# 02_MCU_IO.net
KiCad netlist of a schematic drawn in Altium Designer
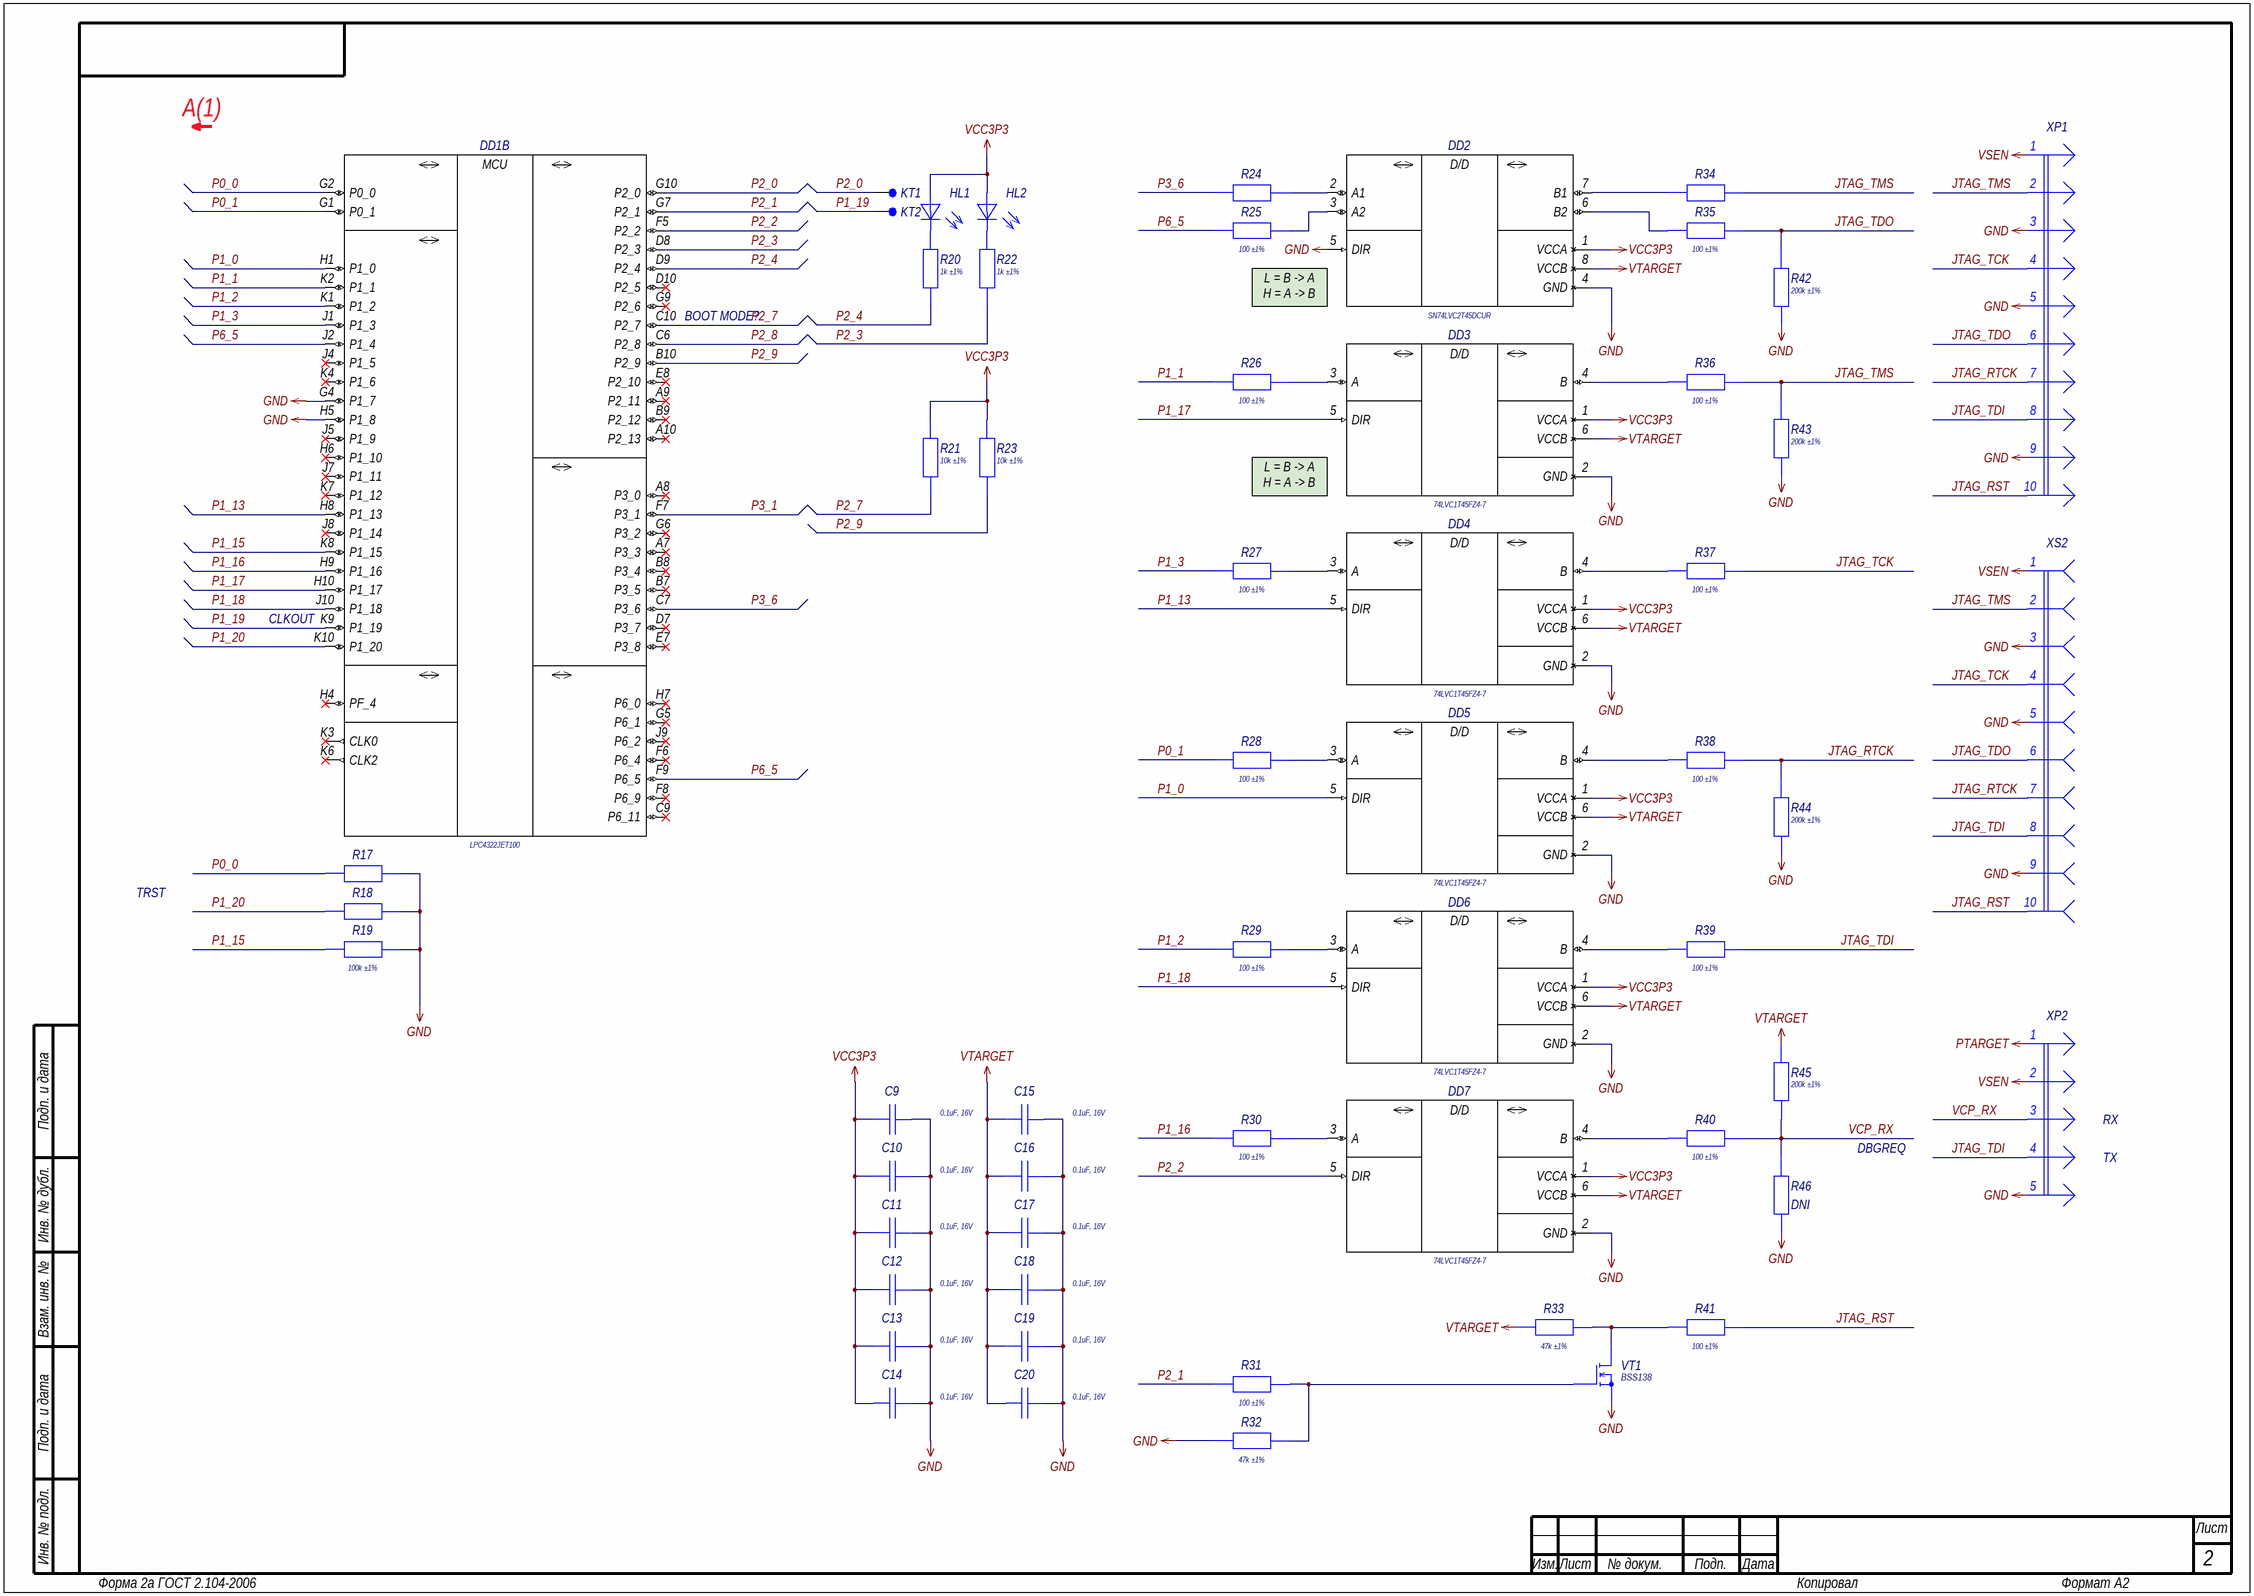
[diagram p0: 02_MCU_IO.SchDoc]

(export (version "E")
  (design (tool "Eeschema 10.0.6"))
  (components
    (comp (ref "C9")
      (value "Capacitor")
      (footprint "C0402_100X050H050_H")
      (fields
        (field (name "PART NUMBER") "GCM155R71C104KA55D")
        (field (name "VOLTAGE") "16V")
        (field (name "TOLERANCE") "±10%")
        (field (name "SCHEMATIC VALUE") "0.1uF, 16V")
      )
      (libsource (lib "ADLib") (part "Capacitor"))
    )
    (comp (ref "C10")
      (value "Capacitor")
      (footprint "C0402_100X050H050_H")
      (fields
        (field (name "PART NUMBER") "GCM155R71C104KA55D")
        (field (name "VOLTAGE") "16V")
        (field (name "TOLERANCE") "±10%")
        (field (name "SCHEMATIC VALUE") "0.1uF, 16V")
      )
      (libsource (lib "ADLib") (part "Capacitor"))
    )
    (comp (ref "C11")
      (value "Capacitor")
      (footprint "C0402_100X050H050_H")
      (fields
        (field (name "PART NUMBER") "GCM155R71C104KA55D")
        (field (name "VOLTAGE") "16V")
        (field (name "TOLERANCE") "±10%")
        (field (name "SCHEMATIC VALUE") "0.1uF, 16V")
      )
      (libsource (lib "ADLib") (part "Capacitor"))
    )
    (comp (ref "C12")
      (value "Capacitor")
      (footprint "C0402_100X050H050_H")
      (fields
        (field (name "PART NUMBER") "GCM155R71C104KA55D")
        (field (name "VOLTAGE") "16V")
        (field (name "TOLERANCE") "±10%")
        (field (name "SCHEMATIC VALUE") "0.1uF, 16V")
      )
      (libsource (lib "ADLib") (part "Capacitor"))
    )
    (comp (ref "C13")
      (value "Capacitor")
      (footprint "C0402_100X050H050_H")
      (fields
        (field (name "PART NUMBER") "GCM155R71C104KA55D")
        (field (name "VOLTAGE") "16V")
        (field (name "TOLERANCE") "±10%")
        (field (name "SCHEMATIC VALUE") "0.1uF, 16V")
      )
      (libsource (lib "ADLib") (part "Capacitor"))
    )
    (comp (ref "C14")
      (value "Capacitor")
      (footprint "C0402_100X050H050_H")
      (fields
        (field (name "PART NUMBER") "GCM155R71C104KA55D")
        (field (name "VOLTAGE") "16V")
        (field (name "TOLERANCE") "±10%")
        (field (name "SCHEMATIC VALUE") "0.1uF, 16V")
      )
      (libsource (lib "ADLib") (part "Capacitor"))
    )
    (comp (ref "C15")
      (value "Capacitor")
      (footprint "C0402_100X050H050_H")
      (fields
        (field (name "PART NUMBER") "GCM155R71C104KA55D")
        (field (name "VOLTAGE") "16V")
        (field (name "TOLERANCE") "±10%")
        (field (name "SCHEMATIC VALUE") "0.1uF, 16V")
      )
      (libsource (lib "ADLib") (part "Capacitor"))
    )
    (comp (ref "C16")
      (value "Capacitor")
      (footprint "C0402_100X050H050_H")
      (fields
        (field (name "PART NUMBER") "GCM155R71C104KA55D")
        (field (name "VOLTAGE") "16V")
        (field (name "TOLERANCE") "±10%")
        (field (name "SCHEMATIC VALUE") "0.1uF, 16V")
      )
      (libsource (lib "ADLib") (part "Capacitor"))
    )
    (comp (ref "C17")
      (value "Capacitor")
      (footprint "C0402_100X050H050_H")
      (fields
        (field (name "PART NUMBER") "GCM155R71C104KA55D")
        (field (name "VOLTAGE") "16V")
        (field (name "TOLERANCE") "±10%")
        (field (name "SCHEMATIC VALUE") "0.1uF, 16V")
      )
      (libsource (lib "ADLib") (part "Capacitor"))
    )
    (comp (ref "C18")
      (value "Capacitor")
      (footprint "C0402_100X050H050_H")
      (fields
        (field (name "PART NUMBER") "GCM155R71C104KA55D")
        (field (name "VOLTAGE") "16V")
        (field (name "TOLERANCE") "±10%")
        (field (name "SCHEMATIC VALUE") "0.1uF, 16V")
      )
      (libsource (lib "ADLib") (part "Capacitor"))
    )
    (comp (ref "C19")
      (value "Capacitor")
      (footprint "C0402_100X050H050_H")
      (fields
        (field (name "PART NUMBER") "GCM155R71C104KA55D")
        (field (name "VOLTAGE") "16V")
        (field (name "TOLERANCE") "±10%")
        (field (name "SCHEMATIC VALUE") "0.1uF, 16V")
      )
      (libsource (lib "ADLib") (part "Capacitor"))
    )
    (comp (ref "C20")
      (value "Capacitor")
      (footprint "C0402_100X050H050_H")
      (fields
        (field (name "PART NUMBER") "GCM155R71C104KA55D")
        (field (name "VOLTAGE") "16V")
        (field (name "TOLERANCE") "±10%")
        (field (name "SCHEMATIC VALUE") "0.1uF, 16V")
      )
      (libsource (lib "ADLib") (part "Capacitor"))
    )
    (comp (ref "DD1")
      (value "LPC43xxJET100-Series")
      (footprint "TFBGA-100_080P900X900X120_N")
      (fields
        (field (name "SCHEMATIC VALUE") "LPC4322JET100")
        (field (name "PART NUMBER") "LPC4322JET100")
        (field (name "MANUFACTURER") "NXP Semiconductors")
      )
      (libsource (lib "ADLib") (part "LPC43xxJET100-Series"))
    )
    (comp (ref "DD2")
      (value "SN74LVC2T45DCx-Series")
      (footprint "VSSOP-8_050P200X230X090_N")
      (fields
        (field (name "PART NUMBER") "SN74LVC2T45DCUR")
        (field (name "LCSC PART") "C15741")
        (field (name "MANUFACTURER") "Texas Instruments")
        (field (name "SCHEMATIC VALUE") "SN74LVC2T45DCUR")
      )
      (libsource (lib "ADLib") (part "SN74LVC2T45DCx-Series"))
    )
    (comp (ref "DD3")
      (value "74LVC1T45x-Series")
      (footprint "X2-DFN-6_050P140X100X040_N")
      (fields
        (field (name "PART NUMBER") "74LVC1T45FZ4-7")
        (field (name "LCSC PART") "C150482")
        (field (name "MANUFACTURER") "Diodes Incorporated")
        (field (name "SCHEMATIC VALUE") "74LVC1T45FZ4-7")
      )
      (libsource (lib "ADLib") (part "74LVC1T45x-Series"))
    )
    (comp (ref "DD4")
      (value "74LVC1T45x-Series")
      (footprint "X2-DFN-6_050P140X100X040_N")
      (fields
        (field (name "PART NUMBER") "74LVC1T45FZ4-7")
        (field (name "LCSC PART") "C150482")
        (field (name "MANUFACTURER") "Diodes Incorporated")
        (field (name "SCHEMATIC VALUE") "74LVC1T45FZ4-7")
      )
      (libsource (lib "ADLib") (part "74LVC1T45x-Series"))
    )
    (comp (ref "DD5")
      (value "74LVC1T45x-Series")
      (footprint "X2-DFN-6_050P140X100X040_N")
      (fields
        (field (name "PART NUMBER") "74LVC1T45FZ4-7")
        (field (name "LCSC PART") "C150482")
        (field (name "MANUFACTURER") "Diodes Incorporated")
        (field (name "SCHEMATIC VALUE") "74LVC1T45FZ4-7")
      )
      (libsource (lib "ADLib") (part "74LVC1T45x-Series"))
    )
    (comp (ref "DD6")
      (value "74LVC1T45x-Series")
      (footprint "X2-DFN-6_050P140X100X040_N")
      (fields
        (field (name "PART NUMBER") "74LVC1T45FZ4-7")
        (field (name "LCSC PART") "C150482")
        (field (name "MANUFACTURER") "Diodes Incorporated")
        (field (name "SCHEMATIC VALUE") "74LVC1T45FZ4-7")
      )
      (libsource (lib "ADLib") (part "74LVC1T45x-Series"))
    )
    (comp (ref "DD7")
      (value "74LVC1T45x-Series")
      (footprint "X2-DFN-6_050P140X100X040_N")
      (fields
        (field (name "PART NUMBER") "74LVC1T45FZ4-7")
        (field (name "LCSC PART") "C150482")
        (field (name "MANUFACTURER") "Diodes Incorporated")
        (field (name "SCHEMATIC VALUE") "74LVC1T45FZ4-7")
      )
      (libsource (lib "ADLib") (part "74LVC1T45x-Series"))
    )
    (comp (ref "HL1")
      (value "Text")
      (footprint "LD0603_L")
      (fields
        (field (name "PART NUMBER") "NCD0603R1")
        (field (name "LCSC PART") "C84263")
        (field (name "MANUFACTURER") "Foshan NationStar Optoelectronics")
        (field (name "PUBLISHER") "Andrew Danich")
      )
      (libsource (lib "ADLib") (part "Led-1"))
    )
    (comp (ref "HL2")
      (value "Text")
      (footprint "LD0603_L")
      (fields
        (field (name "PART NUMBER") "NCD0603G1")
        (field (name "LCSC PART") "C84267")
        (field (name "MANUFACTURER") "Foshan NationStar Optoelectronics")
        (field (name "PUBLISHER") "Andrew Danich")
      )
      (libsource (lib "ADLib") (part "Led-1"))
    )
    (comp (ref "KT1")
      (value "Text")
      (footprint "TP-SMT-C-0.5mm")
      (fields (field (name "PART NUMBER") "TestPoint-SMT") (field (name "PUBLISHER") "Andrew Danich"))
      (libsource (lib "ADLib") (part "TP-S-1"))
    )
    (comp (ref "KT2")
      (value "Text")
      (footprint "TP-SMT-C-0.5mm")
      (fields (field (name "PART NUMBER") "TestPoint-SMT") (field (name "PUBLISHER") "Andrew Danich"))
      (libsource (lib "ADLib") (part "TP-S-1"))
    )
    (comp (ref "R17")
      (value "Resistor")
      (footprint "R0402_100X050H035_H")
      (fields
        (field (name "PART NUMBER") "0402WGF1003TCE")
        (field (name "TOLERANCE") "±1%")
        (field (name "MANUFACTURER") "Uniroyal Elec")
      )
      (libsource (lib "ADLib") (part "Resistor"))
    )
    (comp (ref "R18")
      (value "Resistor")
      (footprint "R0402_100X050H035_H")
      (fields
        (field (name "PART NUMBER") "0402WGF1003TCE")
        (field (name "TOLERANCE") "±1%")
        (field (name "MANUFACTURER") "Uniroyal Elec")
      )
      (libsource (lib "ADLib") (part "Resistor"))
    )
    (comp (ref "R19")
      (value "Resistor")
      (footprint "R0402_100X050H035_H")
      (fields
        (field (name "PART NUMBER") "0402WGF1003TCE")
        (field (name "TOLERANCE") "±1%")
        (field (name "MANUFACTURER") "Uniroyal Elec")
        (field (name "SCHEMATIC VALUE") "100k ±1%")
      )
      (libsource (lib "ADLib") (part "Resistor"))
    )
    (comp (ref "R20")
      (value "Resistor")
      (footprint "R0402_100X050H035_H")
      (fields
        (field (name "PART NUMBER") "0402WGF1001TCE")
        (field (name "TOLERANCE") "±1%")
        (field (name "MANUFACTURER") "Uniroyal Elec")
        (field (name "SCHEMATIC VALUE") "1k ±1%")
      )
      (libsource (lib "ADLib") (part "Resistor"))
    )
    (comp (ref "R21")
      (value "Resistor")
      (footprint "R0402_100X050H035_H")
      (fields
        (field (name "PART NUMBER") "0402WGF1002TCE")
        (field (name "TOLERANCE") "±1%")
        (field (name "MANUFACTURER") "Uniroyal Elec")
        (field (name "SCHEMATIC VALUE") "10k ±1%")
      )
      (libsource (lib "ADLib") (part "Resistor"))
    )
    (comp (ref "R22")
      (value "Resistor")
      (footprint "R0402_100X050H035_H")
      (fields
        (field (name "PART NUMBER") "0402WGF1001TCE")
        (field (name "TOLERANCE") "±1%")
        (field (name "MANUFACTURER") "Uniroyal Elec")
        (field (name "SCHEMATIC VALUE") "1k ±1%")
      )
      (libsource (lib "ADLib") (part "Resistor"))
    )
    (comp (ref "R23")
      (value "Resistor")
      (footprint "R0402_100X050H035_H")
      (fields
        (field (name "PART NUMBER") "0402WGF1002TCE")
        (field (name "TOLERANCE") "±1%")
        (field (name "MANUFACTURER") "Uniroyal Elec")
        (field (name "SCHEMATIC VALUE") "10k ±1%")
      )
      (libsource (lib "ADLib") (part "Resistor"))
    )
    (comp (ref "R24")
      (value "Resistor")
      (footprint "R0402_100X050H035_H")
      (fields
        (field (name "PART NUMBER") "RC0402FR-07100RL")
        (field (name "TOLERANCE") "±1%")
        (field (name "MANUFACTURER") "Yageo")
      )
      (libsource (lib "ADLib") (part "Resistor"))
    )
    (comp (ref "R25")
      (value "Resistor")
      (footprint "R0402_100X050H035_H")
      (fields
        (field (name "PART NUMBER") "RC0402FR-07100RL")
        (field (name "TOLERANCE") "±1%")
        (field (name "MANUFACTURER") "Yageo")
        (field (name "SCHEMATIC VALUE") "100 ±1%")
      )
      (libsource (lib "ADLib") (part "Resistor"))
    )
    (comp (ref "R26")
      (value "Resistor")
      (footprint "R0402_100X050H035_H")
      (fields
        (field (name "PART NUMBER") "RC0402FR-07100RL")
        (field (name "TOLERANCE") "±1%")
        (field (name "MANUFACTURER") "Yageo")
        (field (name "SCHEMATIC VALUE") "100 ±1%")
      )
      (libsource (lib "ADLib") (part "Resistor"))
    )
    (comp (ref "R27")
      (value "Resistor")
      (footprint "R0402_100X050H035_H")
      (fields
        (field (name "PART NUMBER") "RC0402FR-07100RL")
        (field (name "TOLERANCE") "±1%")
        (field (name "MANUFACTURER") "Yageo")
        (field (name "SCHEMATIC VALUE") "100 ±1%")
      )
      (libsource (lib "ADLib") (part "Resistor"))
    )
    (comp (ref "R28")
      (value "Resistor")
      (footprint "R0402_100X050H035_H")
      (fields
        (field (name "PART NUMBER") "RC0402FR-07100RL")
        (field (name "TOLERANCE") "±1%")
        (field (name "MANUFACTURER") "Yageo")
        (field (name "SCHEMATIC VALUE") "100 ±1%")
      )
      (libsource (lib "ADLib") (part "Resistor"))
    )
    (comp (ref "R29")
      (value "Resistor")
      (footprint "R0402_100X050H035_H")
      (fields
        (field (name "PART NUMBER") "RC0402FR-07100RL")
        (field (name "TOLERANCE") "±1%")
        (field (name "MANUFACTURER") "Yageo")
        (field (name "SCHEMATIC VALUE") "100 ±1%")
      )
      (libsource (lib "ADLib") (part "Resistor"))
    )
    (comp (ref "R30")
      (value "Resistor")
      (footprint "R0402_100X050H035_H")
      (fields
        (field (name "PART NUMBER") "RC0402FR-07100RL")
        (field (name "TOLERANCE") "±1%")
        (field (name "MANUFACTURER") "Yageo")
        (field (name "SCHEMATIC VALUE") "100 ±1%")
      )
      (libsource (lib "ADLib") (part "Resistor"))
    )
    (comp (ref "R31")
      (value "Resistor")
      (footprint "R0402_100X050H035_H")
      (fields
        (field (name "PART NUMBER") "RC0402FR-07100RL")
        (field (name "TOLERANCE") "±1%")
        (field (name "MANUFACTURER") "Yageo")
        (field (name "SCHEMATIC VALUE") "100 ±1%")
      )
      (libsource (lib "ADLib") (part "Resistor"))
    )
    (comp (ref "R32")
      (value "Resistor")
      (footprint "R0402_100X050H035_H")
      (fields
        (field (name "PART NUMBER") "0402WGF4702TCE")
        (field (name "TOLERANCE") "±1%")
        (field (name "MANUFACTURER") "Uniroyal Elec")
        (field (name "SCHEMATIC VALUE") "47k ±1%")
      )
      (libsource (lib "ADLib") (part "Resistor"))
    )
    (comp (ref "R33")
      (value "Resistor")
      (footprint "R0402_100X050H035_H")
      (fields
        (field (name "PART NUMBER") "0402WGF4702TCE")
        (field (name "TOLERANCE") "±1%")
        (field (name "MANUFACTURER") "Uniroyal Elec")
        (field (name "SCHEMATIC VALUE") "47k ±1%")
      )
      (libsource (lib "ADLib") (part "Resistor"))
    )
    (comp (ref "R34")
      (value "Resistor")
      (footprint "R0402_100X050H035_H")
      (fields
        (field (name "PART NUMBER") "RC0402FR-07100RL")
        (field (name "TOLERANCE") "±1%")
        (field (name "MANUFACTURER") "Yageo")
      )
      (libsource (lib "ADLib") (part "Resistor"))
    )
    (comp (ref "R35")
      (value "Resistor")
      (footprint "R0402_100X050H035_H")
      (fields
        (field (name "PART NUMBER") "RC0402FR-07100RL")
        (field (name "TOLERANCE") "±1%")
        (field (name "MANUFACTURER") "Yageo")
        (field (name "SCHEMATIC VALUE") "100 ±1%")
      )
      (libsource (lib "ADLib") (part "Resistor"))
    )
    (comp (ref "R36")
      (value "Resistor")
      (footprint "R0402_100X050H035_H")
      (fields
        (field (name "PART NUMBER") "RC0402FR-07100RL")
        (field (name "TOLERANCE") "±1%")
        (field (name "MANUFACTURER") "Yageo")
        (field (name "SCHEMATIC VALUE") "100 ±1%")
      )
      (libsource (lib "ADLib") (part "Resistor"))
    )
    (comp (ref "R37")
      (value "Resistor")
      (footprint "R0402_100X050H035_H")
      (fields
        (field (name "PART NUMBER") "RC0402FR-07100RL")
        (field (name "TOLERANCE") "±1%")
        (field (name "MANUFACTURER") "Yageo")
        (field (name "SCHEMATIC VALUE") "100 ±1%")
      )
      (libsource (lib "ADLib") (part "Resistor"))
    )
    (comp (ref "R38")
      (value "Resistor")
      (footprint "R0402_100X050H035_H")
      (fields
        (field (name "PART NUMBER") "RC0402FR-07100RL")
        (field (name "TOLERANCE") "±1%")
        (field (name "MANUFACTURER") "Yageo")
        (field (name "SCHEMATIC VALUE") "100 ±1%")
      )
      (libsource (lib "ADLib") (part "Resistor"))
    )
    (comp (ref "R39")
      (value "Resistor")
      (footprint "R0402_100X050H035_H")
      (fields
        (field (name "PART NUMBER") "RC0402FR-07100RL")
        (field (name "TOLERANCE") "±1%")
        (field (name "MANUFACTURER") "Yageo")
        (field (name "SCHEMATIC VALUE") "100 ±1%")
      )
      (libsource (lib "ADLib") (part "Resistor"))
    )
    (comp (ref "R40")
      (value "Resistor")
      (footprint "R0402_100X050H035_H")
      (fields
        (field (name "PART NUMBER") "RC0402FR-07100RL")
        (field (name "TOLERANCE") "±1%")
        (field (name "MANUFACTURER") "Yageo")
        (field (name "SCHEMATIC VALUE") "100 ±1%")
      )
      (libsource (lib "ADLib") (part "Resistor"))
    )
    (comp (ref "R41")
      (value "Resistor")
      (footprint "R0402_100X050H035_H")
      (fields
        (field (name "PART NUMBER") "RC0402FR-07100RL")
        (field (name "TOLERANCE") "±1%")
        (field (name "MANUFACTURER") "Yageo")
        (field (name "SCHEMATIC VALUE") "100 ±1%")
      )
      (libsource (lib "ADLib") (part "Resistor"))
    )
    (comp (ref "R42")
      (value "Resistor")
      (footprint "R0402_100X050H035_H")
      (fields
        (field (name "PART NUMBER") "0402WGF2003TCE")
        (field (name "TOLERANCE") "±1%")
        (field (name "MANUFACTURER") "Uniroyal Elec")
        (field (name "SCHEMATIC VALUE") "200k ±1%")
      )
      (libsource (lib "ADLib") (part "Resistor"))
    )
    (comp (ref "R43")
      (value "Resistor")
      (footprint "R0402_100X050H035_H")
      (fields
        (field (name "PART NUMBER") "0402WGF2003TCE")
        (field (name "TOLERANCE") "±1%")
        (field (name "MANUFACTURER") "Uniroyal Elec")
        (field (name "SCHEMATIC VALUE") "200k ±1%")
      )
      (libsource (lib "ADLib") (part "Resistor"))
    )
    (comp (ref "R44")
      (value "Resistor")
      (footprint "R0402_100X050H035_H")
      (fields
        (field (name "PART NUMBER") "0402WGF2003TCE")
        (field (name "TOLERANCE") "±1%")
        (field (name "MANUFACTURER") "Uniroyal Elec")
        (field (name "SCHEMATIC VALUE") "200k ±1%")
      )
      (libsource (lib "ADLib") (part "Resistor"))
    )
    (comp (ref "R45")
      (value "Resistor")
      (footprint "R0402_100X050H035_H")
      (fields
        (field (name "PART NUMBER") "0402WGF2003TCE")
        (field (name "TOLERANCE") "±1%")
        (field (name "MANUFACTURER") "Uniroyal Elec")
        (field (name "SCHEMATIC VALUE") "200k ±1%")
      )
      (libsource (lib "ADLib") (part "Resistor"))
    )
    (comp (ref "R46")
      (value "Resistor")
      (footprint "R0402_100X050H035_H")
      (fields
        (field (name "PART NUMBER") "0402WGF2003TCE")
        (field (name "TOLERANCE") "±1%")
        (field (name "MANUFACTURER") "Uniroyal Elec")
      )
      (libsource (lib "ADLib") (part "Resistor"))
    )
    (comp (ref "VT1")
      (value "MOSFET-N_32")
      (footprint "SOT-23_190P290X160X145_N")
      (fields
        (field (name "SCHEMATIC VALUE") "BSS138")
        (field (name "PART NUMBER") "BSS138")
        (field (name "PUBLISHER") "Andrew Danich")
      )
      (libsource (lib "ADLib") (part "MOSFET-N_32"))
    )
    (comp (ref "XP1")
      (value "Text")
      (footprint "IDC-10MR")
      (fields (field (name "PART NUMBER") "IDC-10MR"))
      (libsource (lib "ADLib") (part "Con-10-M"))
    )
    (comp (ref "XP2")
      (value "Text")
      (footprint "PLS-5RR")
      (fields (field (name "PART NUMBER") "PLS-5R"))
      (libsource (lib "ADLib") (part "Con-5-M"))
    )
    (comp (ref "XS2")
      (value "Text")
      (footprint "XF2M-1015-1A")
      (fields (field (name "PART NUMBER") "XF2M-1015-1A") (field (name "MANUFACTURER") "Omron Electronics"))
      (libsource (lib "ADLib") (part "Con-10-F"))
    )
  )
  (nets
    (net (code "1") (name "/JTAG_RST") (class "Default")
      (node (ref "R41") (pin "2") (pinfunction "2_2") (pintype "passive"))
      (node (ref "XP1") (pin "10") (pintype "passive"))
      (node (ref "XS2") (pin "10") (pintype "passive"))
    )
    (net (code "2") (name "/JTAG_RTCK") (class "Default")
      (node (ref "R38") (pin "2") (pinfunction "2_2") (pintype "passive"))
      (node (ref "R44") (pin "2") (pinfunction "2_2") (pintype "passive"))
      (node (ref "XP1") (pin "7") (pintype "passive"))
      (node (ref "XS2") (pin "7") (pintype "passive"))
    )
    (net (code "3") (name "/JTAG_TCK") (class "Default")
      (node (ref "R37") (pin "2") (pinfunction "2_2") (pintype "passive"))
      (node (ref "XP1") (pin "4") (pintype "passive"))
      (node (ref "XS2") (pin "4") (pintype "passive"))
    )
    (net (code "4") (name "/JTAG_TDI") (class "Default")
      (node (ref "R39") (pin "2") (pinfunction "2_2") (pintype "passive"))
      (node (ref "XP1") (pin "8") (pintype "passive"))
      (node (ref "XP2") (pin "4") (pintype "passive"))
      (node (ref "XS2") (pin "8") (pintype "passive"))
    )
    (net (code "5") (name "/JTAG_TDO") (class "Default")
      (node (ref "R35") (pin "2") (pinfunction "2_2") (pintype "passive"))
      (node (ref "R42") (pin "2") (pinfunction "2_2") (pintype "passive"))
      (node (ref "XP1") (pin "6") (pintype "passive"))
      (node (ref "XS2") (pin "6") (pintype "passive"))
    )
    (net (code "6") (name "/JTAG_TMS") (class "Default")
      (node (ref "R34") (pin "2") (pinfunction "2_2") (pintype "passive"))
      (node (ref "R36") (pin "2") (pinfunction "2_2") (pintype "passive"))
      (node (ref "R43") (pin "2") (pinfunction "2_2") (pintype "passive"))
      (node (ref "XP1") (pin "2") (pintype "passive"))
      (node (ref "XS2") (pin "2") (pintype "passive"))
    )
    (net (code "7") (name "/P0_0") (class "Default")
      (node (ref "DD1") (pin "G2") (pinfunction "P0_0_G2") (pintype "bidirectional"))
      (node (ref "R17") (pin "1") (pinfunction "1_1") (pintype "passive"))
    )
    (net (code "8") (name "/P0_1") (class "Default")
      (node (ref "DD1") (pin "G1") (pinfunction "P0_1_G1") (pintype "bidirectional"))
      (node (ref "R28") (pin "1") (pinfunction "1_1") (pintype "passive"))
    )
    (net (code "9") (name "/P1_0") (class "Default")
      (node (ref "DD1") (pin "H1") (pinfunction "P1_0_H1") (pintype "bidirectional"))
      (node (ref "DD5") (pin "5") (pinfunction "DIR_5") (pintype "input"))
    )
    (net (code "10") (name "/P1_1") (class "Default")
      (node (ref "DD1") (pin "K2") (pinfunction "P1_1_K2") (pintype "bidirectional"))
      (node (ref "R26") (pin "1") (pinfunction "1_1") (pintype "passive"))
    )
    (net (code "11") (name "/P1_2") (class "Default")
      (node (ref "DD1") (pin "K1") (pinfunction "P1_2_K1") (pintype "bidirectional"))
      (node (ref "R29") (pin "1") (pinfunction "1_1") (pintype "passive"))
    )
    (net (code "12") (name "/P1_3") (class "Default")
      (node (ref "DD1") (pin "J1") (pinfunction "P1_3_J1") (pintype "bidirectional"))
      (node (ref "R27") (pin "1") (pinfunction "1_1") (pintype "passive"))
    )
    (net (code "13") (name "/P1_13") (class "Default")
      (node (ref "DD1") (pin "H8") (pinfunction "P1_13_H8") (pintype "bidirectional"))
      (node (ref "DD4") (pin "5") (pinfunction "DIR_5") (pintype "input"))
    )
    (net (code "14") (name "/P1_15") (class "Default")
      (node (ref "DD1") (pin "K8") (pinfunction "P1_15_K8") (pintype "bidirectional"))
      (node (ref "R19") (pin "1") (pinfunction "1_1") (pintype "passive"))
    )
    (net (code "15") (name "/P1_16") (class "Default")
      (node (ref "DD1") (pin "H9") (pinfunction "P1_16_H9") (pintype "bidirectional"))
      (node (ref "R30") (pin "1") (pinfunction "1_1") (pintype "passive"))
    )
    (net (code "16") (name "/P1_17") (class "Default")
      (node (ref "DD1") (pin "H10") (pinfunction "P1_17_H10") (pintype "bidirectional"))
      (node (ref "DD3") (pin "5") (pinfunction "DIR_5") (pintype "input"))
    )
    (net (code "17") (name "/P1_18") (class "Default")
      (node (ref "DD1") (pin "J10") (pinfunction "P1_18_J10") (pintype "bidirectional"))
      (node (ref "DD6") (pin "5") (pinfunction "DIR_5") (pintype "input"))
    )
    (net (code "18") (name "/P1_19") (class "Default")
      (node (ref "DD1") (pin "K9") (pinfunction "P1_19_K9") (pintype "bidirectional"))
      (node (ref "KT2") (pin "1") (pinfunction "1_1") (pintype "passive"))
    )
    (net (code "19") (name "/P1_20") (class "Default")
      (node (ref "DD1") (pin "K10") (pinfunction "P1_20_K10") (pintype "bidirectional"))
      (node (ref "R18") (pin "1") (pinfunction "1_1") (pintype "passive"))
    )
    (net (code "20") (name "/P2_0") (class "Default")
      (node (ref "DD1") (pin "G10") (pinfunction "P2_0_G10") (pintype "bidirectional"))
      (node (ref "KT1") (pin "1") (pinfunction "1_1") (pintype "passive"))
    )
    (net (code "21") (name "/P2_1") (class "Default")
      (node (ref "DD1") (pin "G7") (pinfunction "P2_1_G7") (pintype "bidirectional"))
      (node (ref "R31") (pin "1") (pinfunction "1_1") (pintype "passive"))
    )
    (net (code "22") (name "/P2_2") (class "Default")
      (node (ref "DD1") (pin "F5") (pinfunction "P2_2_F5") (pintype "bidirectional"))
      (node (ref "DD7") (pin "5") (pinfunction "DIR_5") (pintype "input"))
    )
    (net (code "23") (name "/P2_3") (class "Default")
      (node (ref "DD1") (pin "D8") (pinfunction "P2_3_D8") (pintype "bidirectional"))
      (node (ref "R22") (pin "1") (pinfunction "1_1") (pintype "passive"))
    )
    (net (code "24") (name "/P2_4") (class "Default")
      (node (ref "DD1") (pin "D9") (pinfunction "P2_4_D9") (pintype "bidirectional"))
      (node (ref "R20") (pin "1") (pinfunction "1_1") (pintype "passive"))
    )
    (net (code "25") (name "/P2_7") (class "Default")
      (node (ref "DD1") (pin "C10") (pinfunction "P2_7_C10") (pintype "bidirectional"))
      (node (ref "R21") (pin "2") (pinfunction "2_2") (pintype "passive"))
    )
    (net (code "26") (name "/P2_8") (class "Default")
      (node (ref "DD1") (pin "C6") (pinfunction "P2_8_C6") (pintype "bidirectional"))
    )
    (net (code "27") (name "/P2_9") (class "Default")
      (node (ref "DD1") (pin "B10") (pinfunction "P2_9_B10") (pintype "bidirectional"))
      (node (ref "R23") (pin "2") (pinfunction "2_2") (pintype "passive"))
    )
    (net (code "28") (name "/P3_1") (class "Default")
      (node (ref "DD1") (pin "F7") (pinfunction "P3_1_F7") (pintype "bidirectional"))
    )
    (net (code "29") (name "/P3_6") (class "Default")
      (node (ref "DD1") (pin "C7") (pinfunction "P3_6_C7") (pintype "bidirectional"))
      (node (ref "R24") (pin "1") (pinfunction "1_1") (pintype "passive"))
    )
    (net (code "30") (name "/P6_5") (class "Default")
      (node (ref "DD1") (pin "F9") (pinfunction "P6_5_F9") (pintype "bidirectional"))
      (node (ref "DD1") (pin "J2") (pinfunction "P1_4_J2") (pintype "bidirectional"))
      (node (ref "R25") (pin "1") (pinfunction "1_1") (pintype "passive"))
    )
    (net (code "31") (name "/VCP_RX") (class "Default")
      (node (ref "R40") (pin "2") (pinfunction "2_2") (pintype "passive"))
      (node (ref "R45") (pin "1") (pinfunction "1_1") (pintype "passive"))
      (node (ref "R46") (pin "2") (pinfunction "2_2") (pintype "passive"))
      (node (ref "XP2") (pin "3") (pintype "passive"))
    )
    (net (code "32") (name "GND") (class "Default")
      (node (ref "C10") (pin "1") (pinfunction "1_1") (pintype "passive"))
      (node (ref "C11") (pin "1") (pinfunction "1_1") (pintype "passive"))
      (node (ref "C12") (pin "1") (pinfunction "1_1") (pintype "passive"))
      (node (ref "C13") (pin "1") (pinfunction "1_1") (pintype "passive"))
      (node (ref "C14") (pin "1") (pinfunction "1_1") (pintype "passive"))
      (node (ref "C15") (pin "1") (pinfunction "1_1") (pintype "passive"))
      (node (ref "C16") (pin "1") (pinfunction "1_1") (pintype "passive"))
      (node (ref "C17") (pin "1") (pinfunction "1_1") (pintype "passive"))
      (node (ref "C18") (pin "1") (pinfunction "1_1") (pintype "passive"))
      (node (ref "C19") (pin "1") (pinfunction "1_1") (pintype "passive"))
      (node (ref "C20") (pin "1") (pinfunction "1_1") (pintype "passive"))
      (node (ref "C9") (pin "1") (pinfunction "1_1") (pintype "passive"))
      (node (ref "DD1") (pin "G4") (pinfunction "P1_7_G4") (pintype "bidirectional"))
      (node (ref "DD1") (pin "H5") (pinfunction "P1_8_H5") (pintype "bidirectional"))
      (node (ref "DD2") (pin "4") (pinfunction "GND_4") (pintype "power_in"))
      (node (ref "DD2") (pin "5") (pinfunction "DIR_5") (pintype "input"))
      (node (ref "DD3") (pin "2") (pinfunction "GND_2") (pintype "power_in"))
      (node (ref "DD4") (pin "2") (pinfunction "GND_2") (pintype "power_in"))
      (node (ref "DD5") (pin "2") (pinfunction "GND_2") (pintype "power_in"))
      (node (ref "DD6") (pin "2") (pinfunction "GND_2") (pintype "power_in"))
      (node (ref "DD7") (pin "2") (pinfunction "GND_2") (pintype "power_in"))
      (node (ref "R17") (pin "2") (pinfunction "2_2") (pintype "passive"))
      (node (ref "R18") (pin "2") (pinfunction "2_2") (pintype "passive"))
      (node (ref "R19") (pin "2") (pinfunction "2_2") (pintype "passive"))
      (node (ref "R32") (pin "2") (pinfunction "2_2") (pintype "passive"))
      (node (ref "R42") (pin "1") (pinfunction "1_1") (pintype "passive"))
      (node (ref "R43") (pin "1") (pinfunction "1_1") (pintype "passive"))
      (node (ref "R44") (pin "1") (pinfunction "1_1") (pintype "passive"))
      (node (ref "R46") (pin "1") (pinfunction "1_1") (pintype "passive"))
      (node (ref "VT1") (pin "2") (pinfunction "S_2") (pintype "passive"))
      (node (ref "XP1") (pin "3") (pintype "passive"))
      (node (ref "XP1") (pin "5") (pintype "passive"))
      (node (ref "XP1") (pin "9") (pintype "passive"))
      (node (ref "XP2") (pin "5") (pintype "passive"))
      (node (ref "XS2") (pin "3") (pintype "passive"))
      (node (ref "XS2") (pin "5") (pintype "passive"))
      (node (ref "XS2") (pin "9") (pintype "passive"))
    )
    (net (code "33") (name "Net-(DD2-A1)") (class "Default")
      (node (ref "DD2") (pin "2") (pinfunction "A1_2") (pintype "bidirectional"))
      (node (ref "R24") (pin "2") (pinfunction "2_2") (pintype "passive"))
    )
    (net (code "34") (name "Net-(DD2-A2)") (class "Default")
      (node (ref "DD2") (pin "3") (pinfunction "A2_3") (pintype "bidirectional"))
      (node (ref "R25") (pin "2") (pinfunction "2_2") (pintype "passive"))
    )
    (net (code "35") (name "Net-(DD2-B1)") (class "Default")
      (node (ref "DD2") (pin "7") (pinfunction "B1_7") (pintype "bidirectional"))
      (node (ref "R34") (pin "1") (pinfunction "1_1") (pintype "passive"))
    )
    (net (code "36") (name "Net-(DD2-B2)") (class "Default")
      (node (ref "DD2") (pin "6") (pinfunction "B2_6") (pintype "bidirectional"))
      (node (ref "R35") (pin "1") (pinfunction "1_1") (pintype "passive"))
    )
    (net (code "37") (name "Net-(DD3-A)") (class "Default")
      (node (ref "DD3") (pin "3") (pinfunction "A_3") (pintype "bidirectional"))
      (node (ref "R26") (pin "2") (pinfunction "2_2") (pintype "passive"))
    )
    (net (code "38") (name "Net-(DD3-B)") (class "Default")
      (node (ref "DD3") (pin "4") (pinfunction "B_4") (pintype "bidirectional"))
      (node (ref "R36") (pin "1") (pinfunction "1_1") (pintype "passive"))
    )
    (net (code "39") (name "Net-(DD4-A)") (class "Default")
      (node (ref "DD4") (pin "3") (pinfunction "A_3") (pintype "bidirectional"))
      (node (ref "R27") (pin "2") (pinfunction "2_2") (pintype "passive"))
    )
    (net (code "40") (name "Net-(DD4-B)") (class "Default")
      (node (ref "DD4") (pin "4") (pinfunction "B_4") (pintype "bidirectional"))
      (node (ref "R37") (pin "1") (pinfunction "1_1") (pintype "passive"))
    )
    (net (code "41") (name "Net-(DD5-A)") (class "Default")
      (node (ref "DD5") (pin "3") (pinfunction "A_3") (pintype "bidirectional"))
      (node (ref "R28") (pin "2") (pinfunction "2_2") (pintype "passive"))
    )
    (net (code "42") (name "Net-(DD5-B)") (class "Default")
      (node (ref "DD5") (pin "4") (pinfunction "B_4") (pintype "bidirectional"))
      (node (ref "R38") (pin "1") (pinfunction "1_1") (pintype "passive"))
    )
    (net (code "43") (name "Net-(DD6-A)") (class "Default")
      (node (ref "DD6") (pin "3") (pinfunction "A_3") (pintype "bidirectional"))
      (node (ref "R29") (pin "2") (pinfunction "2_2") (pintype "passive"))
    )
    (net (code "44") (name "Net-(DD6-B)") (class "Default")
      (node (ref "DD6") (pin "4") (pinfunction "B_4") (pintype "bidirectional"))
      (node (ref "R39") (pin "1") (pinfunction "1_1") (pintype "passive"))
    )
    (net (code "45") (name "Net-(DD7-A)") (class "Default")
      (node (ref "DD7") (pin "3") (pinfunction "A_3") (pintype "bidirectional"))
      (node (ref "R30") (pin "2") (pinfunction "2_2") (pintype "passive"))
    )
    (net (code "46") (name "Net-(DD7-B)") (class "Default")
      (node (ref "DD7") (pin "4") (pinfunction "B_4") (pintype "bidirectional"))
      (node (ref "R40") (pin "1") (pinfunction "1_1") (pintype "passive"))
    )
    (net (code "47") (name "Net-(HL1-Pad2)") (class "Default")
      (node (ref "HL1") (pin "2") (pintype "passive"))
      (node (ref "R20") (pin "2") (pinfunction "2_2") (pintype "passive"))
    )
    (net (code "48") (name "Net-(HL2-Pad2)") (class "Default")
      (node (ref "HL2") (pin "2") (pintype "passive"))
      (node (ref "R22") (pin "2") (pinfunction "2_2") (pintype "passive"))
    )
    (net (code "49") (name "Net-(VT1-D)") (class "Default")
      (node (ref "R33") (pin "1") (pinfunction "1_1") (pintype "passive"))
      (node (ref "R41") (pin "1") (pinfunction "1_1") (pintype "passive"))
      (node (ref "VT1") (pin "3") (pinfunction "D_3") (pintype "passive"))
    )
    (net (code "50") (name "Net-(VT1-G)") (class "Default")
      (node (ref "R31") (pin "2") (pinfunction "2_2") (pintype "passive"))
      (node (ref "R32") (pin "1") (pinfunction "1_1") (pintype "passive"))
      (node (ref "VT1") (pin "1") (pinfunction "G_1") (pintype "passive"))
    )
    (net (code "51") (name "PTARGET") (class "Default") (node (ref "XP2") (pin "1") (pintype "passive")))
    (net (code "52") (name "VCC3P3") (class "Default")
      (node (ref "C10") (pin "2") (pinfunction "2_2") (pintype "passive"))
      (node (ref "C11") (pin "2") (pinfunction "2_2") (pintype "passive"))
      (node (ref "C12") (pin "2") (pinfunction "2_2") (pintype "passive"))
      (node (ref "C13") (pin "2") (pinfunction "2_2") (pintype "passive"))
      (node (ref "C14") (pin "2") (pinfunction "2_2") (pintype "passive"))
      (node (ref "C9") (pin "2") (pinfunction "2_2") (pintype "passive"))
      (node (ref "DD2") (pin "1") (pinfunction "VCCA_1") (pintype "power_in"))
      (node (ref "DD3") (pin "1") (pinfunction "VCCA_1") (pintype "power_in"))
      (node (ref "DD4") (pin "1") (pinfunction "VCCA_1") (pintype "power_in"))
      (node (ref "DD5") (pin "1") (pinfunction "VCCA_1") (pintype "power_in"))
      (node (ref "DD6") (pin "1") (pinfunction "VCCA_1") (pintype "power_in"))
      (node (ref "DD7") (pin "1") (pinfunction "VCCA_1") (pintype "power_in"))
      (node (ref "HL1") (pin "1") (pintype "passive"))
      (node (ref "HL2") (pin "1") (pintype "passive"))
      (node (ref "R21") (pin "1") (pinfunction "1_1") (pintype "passive"))
      (node (ref "R23") (pin "1") (pinfunction "1_1") (pintype "passive"))
    )
    (net (code "53") (name "VSEN") (class "Default")
      (node (ref "XP1") (pin "1") (pintype "passive"))
      (node (ref "XP2") (pin "2") (pintype "passive"))
      (node (ref "XS2") (pin "1") (pintype "passive"))
    )
    (net (code "54") (name "VTARGET") (class "Default")
      (node (ref "C15") (pin "2") (pinfunction "2_2") (pintype "passive"))
      (node (ref "C16") (pin "2") (pinfunction "2_2") (pintype "passive"))
      (node (ref "C17") (pin "2") (pinfunction "2_2") (pintype "passive"))
      (node (ref "C18") (pin "2") (pinfunction "2_2") (pintype "passive"))
      (node (ref "C19") (pin "2") (pinfunction "2_2") (pintype "passive"))
      (node (ref "C20") (pin "2") (pinfunction "2_2") (pintype "passive"))
      (node (ref "DD2") (pin "8") (pinfunction "VCCB_8") (pintype "power_in"))
      (node (ref "DD3") (pin "6") (pinfunction "VCCB_6") (pintype "power_in"))
      (node (ref "DD4") (pin "6") (pinfunction "VCCB_6") (pintype "power_in"))
      (node (ref "DD5") (pin "6") (pinfunction "VCCB_6") (pintype "power_in"))
      (node (ref "DD6") (pin "6") (pinfunction "VCCB_6") (pintype "power_in"))
      (node (ref "DD7") (pin "6") (pinfunction "VCCB_6") (pintype "power_in"))
      (node (ref "R33") (pin "2") (pinfunction "2_2") (pintype "passive"))
      (node (ref "R45") (pin "2") (pinfunction "2_2") (pintype "passive"))
    )
    (net (code "55") (name "unconnected-(DD1B-CLK0-PadK3)") (class "Default")
      (node (ref "DD1") (pin "K3") (pinfunction "CLK0_K3") (pintype "output+no_connect"))
    )
    (net (code "56") (name "unconnected-(DD1B-CLK2-PadK6)") (class "Default")
      (node (ref "DD1") (pin "K6") (pinfunction "CLK2_K6") (pintype "output+no_connect"))
    )
    (net (code "57") (name "unconnected-(DD1B-P1_5-PadJ4)") (class "Default")
      (node (ref "DD1") (pin "J4") (pinfunction "P1_5_J4") (pintype "bidirectional+no_connect"))
    )
    (net (code "58") (name "unconnected-(DD1B-P1_6-PadK4)") (class "Default")
      (node (ref "DD1") (pin "K4") (pinfunction "P1_6_K4") (pintype "bidirectional+no_connect"))
    )
    (net (code "59") (name "unconnected-(DD1B-P1_9-PadJ5)") (class "Default")
      (node (ref "DD1") (pin "J5") (pinfunction "P1_9_J5") (pintype "bidirectional+no_connect"))
    )
    (net (code "60") (name "unconnected-(DD1B-P1_10-PadH6)") (class "Default")
      (node (ref "DD1") (pin "H6") (pinfunction "P1_10_H6") (pintype "bidirectional+no_connect"))
    )
    (net (code "61") (name "unconnected-(DD1B-P1_11-PadJ7)") (class "Default")
      (node (ref "DD1") (pin "J7") (pinfunction "P1_11_J7") (pintype "bidirectional+no_connect"))
    )
    (net (code "62") (name "unconnected-(DD1B-P1_12-PadK7)") (class "Default")
      (node (ref "DD1") (pin "K7") (pinfunction "P1_12_K7") (pintype "bidirectional+no_connect"))
    )
    (net (code "63") (name "unconnected-(DD1B-P1_14-PadJ8)") (class "Default")
      (node (ref "DD1") (pin "J8") (pinfunction "P1_14_J8") (pintype "bidirectional+no_connect"))
    )
    (net (code "64") (name "unconnected-(DD1B-P2_5-PadD10)") (class "Default")
      (node (ref "DD1") (pin "D10") (pinfunction "P2_5_D10") (pintype "bidirectional+no_connect"))
    )
    (net (code "65") (name "unconnected-(DD1B-P2_6-PadG9)") (class "Default")
      (node (ref "DD1") (pin "G9") (pinfunction "P2_6_G9") (pintype "bidirectional+no_connect"))
    )
    (net (code "66") (name "unconnected-(DD1B-P2_10-PadE8)") (class "Default")
      (node (ref "DD1") (pin "E8") (pinfunction "P2_10_E8") (pintype "bidirectional+no_connect"))
    )
    (net (code "67") (name "unconnected-(DD1B-P2_11-PadA9)") (class "Default")
      (node (ref "DD1") (pin "A9") (pinfunction "P2_11_A9") (pintype "bidirectional+no_connect"))
    )
    (net (code "68") (name "unconnected-(DD1B-P2_12-PadB9)") (class "Default")
      (node (ref "DD1") (pin "B9") (pinfunction "P2_12_B9") (pintype "bidirectional+no_connect"))
    )
    (net (code "69") (name "unconnected-(DD1B-P2_13-PadA10)") (class "Default")
      (node (ref "DD1") (pin "A10") (pinfunction "P2_13_A10") (pintype "bidirectional+no_connect"))
    )
    (net (code "70") (name "unconnected-(DD1B-P3_0-PadA8)") (class "Default")
      (node (ref "DD1") (pin "A8") (pinfunction "P3_0_A8") (pintype "bidirectional+no_connect"))
    )
    (net (code "71") (name "unconnected-(DD1B-P3_2-PadG6)") (class "Default")
      (node (ref "DD1") (pin "G6") (pinfunction "P3_2_G6") (pintype "bidirectional+no_connect"))
    )
    (net (code "72") (name "unconnected-(DD1B-P3_3-PadA7)") (class "Default")
      (node (ref "DD1") (pin "A7") (pinfunction "P3_3_A7") (pintype "bidirectional+no_connect"))
    )
    (net (code "73") (name "unconnected-(DD1B-P3_4-PadB8)") (class "Default")
      (node (ref "DD1") (pin "B8") (pinfunction "P3_4_B8") (pintype "bidirectional+no_connect"))
    )
    (net (code "74") (name "unconnected-(DD1B-P3_5-PadB7)") (class "Default")
      (node (ref "DD1") (pin "B7") (pinfunction "P3_5_B7") (pintype "bidirectional+no_connect"))
    )
    (net (code "75") (name "unconnected-(DD1B-P3_7-PadD7)") (class "Default")
      (node (ref "DD1") (pin "D7") (pinfunction "P3_7_D7") (pintype "bidirectional+no_connect"))
    )
    (net (code "76") (name "unconnected-(DD1B-P3_8-PadE7)") (class "Default")
      (node (ref "DD1") (pin "E7") (pinfunction "P3_8_E7") (pintype "bidirectional+no_connect"))
    )
    (net (code "77") (name "unconnected-(DD1B-P6_0-PadH7)") (class "Default")
      (node (ref "DD1") (pin "H7") (pinfunction "P6_0_H7") (pintype "bidirectional+no_connect"))
    )
    (net (code "78") (name "unconnected-(DD1B-P6_1-PadG5)") (class "Default")
      (node (ref "DD1") (pin "G5") (pinfunction "P6_1_G5") (pintype "bidirectional+no_connect"))
    )
    (net (code "79") (name "unconnected-(DD1B-P6_2-PadJ9)") (class "Default")
      (node (ref "DD1") (pin "J9") (pinfunction "P6_2_J9") (pintype "bidirectional+no_connect"))
    )
    (net (code "80") (name "unconnected-(DD1B-P6_4-PadF6)") (class "Default")
      (node (ref "DD1") (pin "F6") (pinfunction "P6_4_F6") (pintype "bidirectional+no_connect"))
    )
    (net (code "81") (name "unconnected-(DD1B-P6_9-PadF8)") (class "Default")
      (node (ref "DD1") (pin "F8") (pinfunction "P6_9_F8") (pintype "bidirectional+no_connect"))
    )
    (net (code "82") (name "unconnected-(DD1B-P6_11-PadC9)") (class "Default")
      (node (ref "DD1") (pin "C9") (pinfunction "P6_11_C9") (pintype "bidirectional+no_connect"))
    )
    (net (code "83") (name "unconnected-(DD1B-PF_4-PadH4)") (class "Default")
      (node (ref "DD1") (pin "H4") (pinfunction "PF_4_H4") (pintype "bidirectional+no_connect"))
    )
  )
)
